# S111X.net
KiCad netlist of a schematic drawn in EAGLE
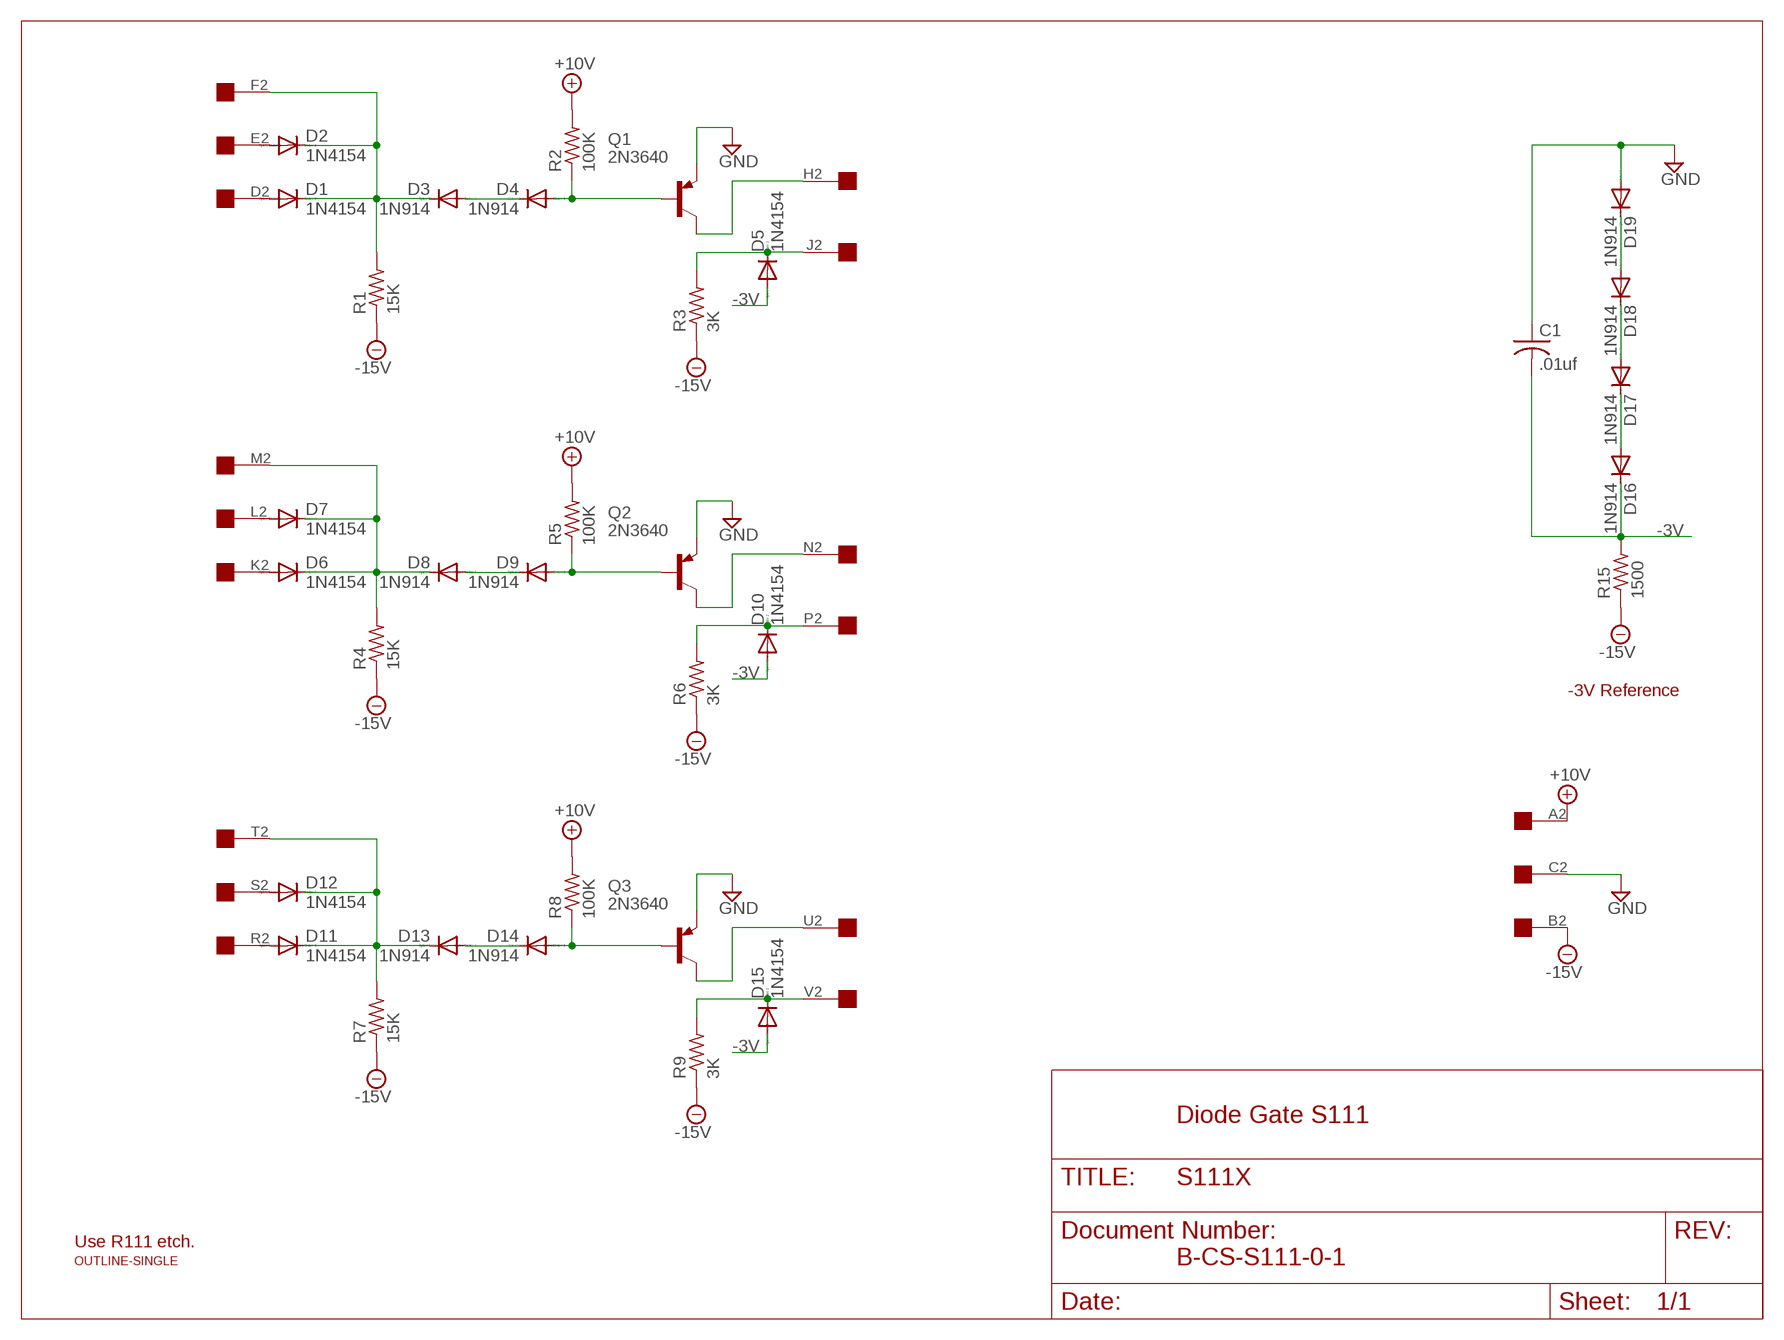
[diagram p0: schematic, sheet 1]

(export (version "E")
  (design (tool "Eeschema 10.0.6"))
  (components
    (comp (ref "C1")
      (value ".01uf")
      (footprint "eagle-import:C050-025X075")
      (libsource (lib "eagle-import") (part "C-US050-025X075"))
    )
    (comp (ref "D1")
      (value "1N4154")
      (footprint "eagle-import:DO35-10")
      (libsource (lib "eagle-import") (part "1N4148DO35-10"))
    )
    (comp (ref "D2")
      (value "1N4154")
      (footprint "eagle-import:DO35-10")
      (libsource (lib "eagle-import") (part "1N4148DO35-10"))
    )
    (comp (ref "D3")
      (value "1N914")
      (footprint "eagle-import:DO35-10")
      (libsource (lib "eagle-import") (part "1N4148DO35-10"))
    )
    (comp (ref "D4")
      (value "1N914")
      (footprint "eagle-import:DO35-10")
      (libsource (lib "eagle-import") (part "1N4148DO35-10"))
    )
    (comp (ref "D5")
      (value "1N4154")
      (footprint "eagle-import:DO35-10")
      (libsource (lib "eagle-import") (part "1N4148DO35-10"))
    )
    (comp (ref "D6")
      (value "1N4154")
      (footprint "eagle-import:DO35-10")
      (libsource (lib "eagle-import") (part "1N4148DO35-10"))
    )
    (comp (ref "D7")
      (value "1N4154")
      (footprint "eagle-import:DO35-10")
      (libsource (lib "eagle-import") (part "1N4148DO35-10"))
    )
    (comp (ref "D8")
      (value "1N914")
      (footprint "eagle-import:DO35-10")
      (libsource (lib "eagle-import") (part "1N4148DO35-10"))
    )
    (comp (ref "D9")
      (value "1N914")
      (footprint "eagle-import:DO35-10")
      (libsource (lib "eagle-import") (part "1N4148DO35-10"))
    )
    (comp (ref "D10")
      (value "1N4154")
      (footprint "eagle-import:DO35-10")
      (libsource (lib "eagle-import") (part "1N4148DO35-10"))
    )
    (comp (ref "D11")
      (value "1N4154")
      (footprint "eagle-import:DO35-10")
      (libsource (lib "eagle-import") (part "1N4148DO35-10"))
    )
    (comp (ref "D12")
      (value "1N4154")
      (footprint "eagle-import:DO35-10")
      (libsource (lib "eagle-import") (part "1N4148DO35-10"))
    )
    (comp (ref "D13")
      (value "1N914")
      (footprint "eagle-import:DO35-10")
      (libsource (lib "eagle-import") (part "1N4148DO35-10"))
    )
    (comp (ref "D14")
      (value "1N914")
      (footprint "eagle-import:DO35-10")
      (libsource (lib "eagle-import") (part "1N4148DO35-10"))
    )
    (comp (ref "D15")
      (value "1N4154")
      (footprint "eagle-import:DO35-10")
      (libsource (lib "eagle-import") (part "1N4148DO35-10"))
    )
    (comp (ref "D16")
      (value "1N914")
      (footprint "eagle-import:DO35-10")
      (libsource (lib "eagle-import") (part "1N4148DO35-10"))
    )
    (comp (ref "D17")
      (value "1N914")
      (footprint "eagle-import:DO35-10")
      (libsource (lib "eagle-import") (part "1N4148DO35-10"))
    )
    (comp (ref "D18")
      (value "1N914")
      (footprint "eagle-import:DO35-10")
      (libsource (lib "eagle-import") (part "1N4148DO35-10"))
    )
    (comp (ref "D19")
      (value "1N914")
      (footprint "eagle-import:DO35-10")
      (libsource (lib "eagle-import") (part "1N4148DO35-10"))
    )
    (comp (ref "Q1")
      (value "2N3640")
      (footprint "eagle-import:TO39")
      (libsource (lib "eagle-import") (part "2N3637"))
    )
    (comp (ref "Q2")
      (value "2N3640")
      (footprint "eagle-import:TO39")
      (libsource (lib "eagle-import") (part "2N3637"))
    )
    (comp (ref "Q3")
      (value "2N3640")
      (footprint "eagle-import:TO39")
      (libsource (lib "eagle-import") (part "2N3637"))
    )
    (comp (ref "R1")
      (value "15K")
      (footprint "eagle-import:0207_10")
      (libsource (lib "eagle-import") (part "R-US_0207/10"))
    )
    (comp (ref "R2")
      (value "100K")
      (footprint "eagle-import:0207_10")
      (libsource (lib "eagle-import") (part "R-US_0207/10"))
    )
    (comp (ref "R3")
      (value "3K")
      (footprint "eagle-import:0207_10")
      (libsource (lib "eagle-import") (part "R-US_0207/10"))
    )
    (comp (ref "R4")
      (value "15K")
      (footprint "eagle-import:0207_10")
      (libsource (lib "eagle-import") (part "R-US_0207/10"))
    )
    (comp (ref "R5")
      (value "100K")
      (footprint "eagle-import:0207_10")
      (libsource (lib "eagle-import") (part "R-US_0207/10"))
    )
    (comp (ref "R6")
      (value "3K")
      (footprint "eagle-import:0207_10")
      (libsource (lib "eagle-import") (part "R-US_0207/10"))
    )
    (comp (ref "R7")
      (value "15K")
      (footprint "eagle-import:0207_10")
      (libsource (lib "eagle-import") (part "R-US_0207/10"))
    )
    (comp (ref "R8")
      (value "100K")
      (footprint "eagle-import:0207_10")
      (libsource (lib "eagle-import") (part "R-US_0207/10"))
    )
    (comp (ref "R9")
      (value "3K")
      (footprint "eagle-import:0207_10")
      (libsource (lib "eagle-import") (part "R-US_0207/10"))
    )
    (comp (ref "R15")
      (value "1500")
      (footprint "eagle-import:0207_10")
      (libsource (lib "eagle-import") (part "R-US_0207/10"))
    )
    (comp (ref "U$1")
      (value "OUTLINE-SINGLE")
      (footprint "eagle-import:SINGLE")
      (libsource (lib "eagle-import") (part "OUTLINE-SINGLE"))
    )
    (comp (ref "U$2")
      (value "EDGE-1")
      (footprint "eagle-import:EDGE-CON1")
      (libsource (lib "eagle-import") (part "EDGE-1"))
    )
  )
  (nets
    (net (code "1") (name "+10V") (class "Default")
      (node (ref "R2") (pin "2") (pinfunction "2_2") (pintype "passive"))
      (node (ref "R5") (pin "2") (pinfunction "2_2") (pintype "passive"))
      (node (ref "R8") (pin "2") (pinfunction "2_2") (pintype "passive"))
      (node (ref "U$2") (pin "A2") (pinfunction "1_A2") (pintype "bidirectional"))
    )
    (net (code "2") (name "-15V") (class "Default")
      (node (ref "R1") (pin "1") (pinfunction "1_1") (pintype "passive"))
      (node (ref "R15") (pin "1") (pinfunction "1_1") (pintype "passive"))
      (node (ref "R3") (pin "1") (pinfunction "1_1") (pintype "passive"))
      (node (ref "R4") (pin "1") (pinfunction "1_1") (pintype "passive"))
      (node (ref "R6") (pin "1") (pinfunction "1_1") (pintype "passive"))
      (node (ref "R7") (pin "1") (pinfunction "1_1") (pintype "passive"))
      (node (ref "R9") (pin "1") (pinfunction "1_1") (pintype "passive"))
      (node (ref "U$2") (pin "B2") (pinfunction "1_B2") (pintype "bidirectional"))
    )
    (net (code "3") (name "/-3V") (class "Default")
      (node (ref "C1") (pin "2") (pinfunction "2_2") (pintype "passive"))
      (node (ref "D10") (pin "A") (pinfunction "A_A") (pintype "passive"))
      (node (ref "D15") (pin "A") (pinfunction "A_A") (pintype "passive"))
      (node (ref "D16") (pin "C") (pinfunction "C_C") (pintype "passive"))
      (node (ref "D5") (pin "A") (pinfunction "A_A") (pintype "passive"))
      (node (ref "R15") (pin "2") (pinfunction "2_2") (pintype "passive"))
    )
    (net (code "4") (name "GND") (class "Default")
      (node (ref "C1") (pin "1") (pinfunction "1_1") (pintype "passive"))
      (node (ref "D19") (pin "A") (pinfunction "A_A") (pintype "passive"))
      (node (ref "Q1") (pin "1") (pinfunction "E_1") (pintype "passive"))
      (node (ref "Q2") (pin "1") (pinfunction "E_1") (pintype "passive"))
      (node (ref "Q3") (pin "1") (pinfunction "E_1") (pintype "passive"))
      (node (ref "U$2") (pin "C2") (pinfunction "1_C2") (pintype "bidirectional"))
    )
    (net (code "5") (name "Net-(D3-PadA)") (class "Default")
      (node (ref "D3") (pin "A") (pinfunction "A_A") (pintype "passive"))
      (node (ref "D4") (pin "C") (pinfunction "C_C") (pintype "passive"))
    )
    (net (code "6") (name "Net-(D8-PadA)") (class "Default")
      (node (ref "D8") (pin "A") (pinfunction "A_A") (pintype "passive"))
      (node (ref "D9") (pin "C") (pinfunction "C_C") (pintype "passive"))
    )
    (net (code "7") (name "Net-(D13-PadA)") (class "Default")
      (node (ref "D13") (pin "A") (pinfunction "A_A") (pintype "passive"))
      (node (ref "D14") (pin "C") (pinfunction "C_C") (pintype "passive"))
    )
    (net (code "8") (name "Net-(D16-PadA)") (class "Default")
      (node (ref "D16") (pin "A") (pinfunction "A_A") (pintype "passive"))
      (node (ref "D17") (pin "C") (pinfunction "C_C") (pintype "passive"))
    )
    (net (code "9") (name "Net-(D17-PadA)") (class "Default")
      (node (ref "D17") (pin "A") (pinfunction "A_A") (pintype "passive"))
      (node (ref "D18") (pin "C") (pinfunction "C_C") (pintype "passive"))
    )
    (net (code "10") (name "Net-(D18-PadA)") (class "Default")
      (node (ref "D18") (pin "A") (pinfunction "A_A") (pintype "passive"))
      (node (ref "D19") (pin "C") (pinfunction "C_C") (pintype "passive"))
    )
    (net (code "11") (name "Net-(Q1-B)") (class "Default")
      (node (ref "D4") (pin "A") (pinfunction "A_A") (pintype "passive"))
      (node (ref "Q1") (pin "2") (pinfunction "B_2") (pintype "passive"))
      (node (ref "R2") (pin "1") (pinfunction "1_1") (pintype "passive"))
    )
    (net (code "12") (name "Net-(Q1-C)") (class "Default")
      (node (ref "Q1") (pin "3") (pinfunction "C_3") (pintype "passive"))
      (node (ref "U$2") (pin "H2") (pinfunction "1_H2") (pintype "bidirectional"))
    )
    (net (code "13") (name "Net-(Q2-B)") (class "Default")
      (node (ref "D9") (pin "A") (pinfunction "A_A") (pintype "passive"))
      (node (ref "Q2") (pin "2") (pinfunction "B_2") (pintype "passive"))
      (node (ref "R5") (pin "1") (pinfunction "1_1") (pintype "passive"))
    )
    (net (code "14") (name "Net-(Q2-C)") (class "Default")
      (node (ref "Q2") (pin "3") (pinfunction "C_3") (pintype "passive"))
      (node (ref "U$2") (pin "N2") (pinfunction "1_N2") (pintype "bidirectional"))
    )
    (net (code "15") (name "Net-(Q3-B)") (class "Default")
      (node (ref "D14") (pin "A") (pinfunction "A_A") (pintype "passive"))
      (node (ref "Q3") (pin "2") (pinfunction "B_2") (pintype "passive"))
      (node (ref "R8") (pin "1") (pinfunction "1_1") (pintype "passive"))
    )
    (net (code "16") (name "Net-(Q3-C)") (class "Default")
      (node (ref "Q3") (pin "3") (pinfunction "C_3") (pintype "passive"))
      (node (ref "U$2") (pin "U2") (pinfunction "1_U2") (pintype "bidirectional"))
    )
    (net (code "17") (name "Net-(U$2D-1)") (class "Default")
      (node (ref "D1") (pin "A") (pinfunction "A_A") (pintype "passive"))
      (node (ref "U$2") (pin "D2") (pinfunction "1_D2") (pintype "bidirectional"))
    )
    (net (code "18") (name "Net-(U$2E-1)") (class "Default")
      (node (ref "D2") (pin "A") (pinfunction "A_A") (pintype "passive"))
      (node (ref "U$2") (pin "E2") (pinfunction "1_E2") (pintype "bidirectional"))
    )
    (net (code "19") (name "Net-(U$2F-1)") (class "Default")
      (node (ref "D1") (pin "C") (pinfunction "C_C") (pintype "passive"))
      (node (ref "D2") (pin "C") (pinfunction "C_C") (pintype "passive"))
      (node (ref "D3") (pin "C") (pinfunction "C_C") (pintype "passive"))
      (node (ref "R1") (pin "2") (pinfunction "2_2") (pintype "passive"))
      (node (ref "U$2") (pin "F2") (pinfunction "1_F2") (pintype "bidirectional"))
    )
    (net (code "20") (name "Net-(U$2H-1)") (class "Default")
      (node (ref "D5") (pin "C") (pinfunction "C_C") (pintype "passive"))
      (node (ref "R3") (pin "2") (pinfunction "2_2") (pintype "passive"))
      (node (ref "U$2") (pin "J2") (pinfunction "1_J2") (pintype "bidirectional"))
    )
    (net (code "21") (name "Net-(U$2I-1)") (class "Default")
      (node (ref "D6") (pin "A") (pinfunction "A_A") (pintype "passive"))
      (node (ref "U$2") (pin "K2") (pinfunction "1_K2") (pintype "bidirectional"))
    )
    (net (code "22") (name "Net-(U$2J-1)") (class "Default")
      (node (ref "D7") (pin "A") (pinfunction "A_A") (pintype "passive"))
      (node (ref "U$2") (pin "L2") (pinfunction "1_L2") (pintype "bidirectional"))
    )
    (net (code "23") (name "Net-(U$2K-1)") (class "Default")
      (node (ref "D6") (pin "C") (pinfunction "C_C") (pintype "passive"))
      (node (ref "D7") (pin "C") (pinfunction "C_C") (pintype "passive"))
      (node (ref "D8") (pin "C") (pinfunction "C_C") (pintype "passive"))
      (node (ref "R4") (pin "2") (pinfunction "2_2") (pintype "passive"))
      (node (ref "U$2") (pin "M2") (pinfunction "1_M2") (pintype "bidirectional"))
    )
    (net (code "24") (name "Net-(U$2M-1)") (class "Default")
      (node (ref "D10") (pin "C") (pinfunction "C_C") (pintype "passive"))
      (node (ref "R6") (pin "2") (pinfunction "2_2") (pintype "passive"))
      (node (ref "U$2") (pin "P2") (pinfunction "1_P2") (pintype "bidirectional"))
    )
    (net (code "25") (name "Net-(U$2N-1)") (class "Default")
      (node (ref "D11") (pin "A") (pinfunction "A_A") (pintype "passive"))
      (node (ref "U$2") (pin "R2") (pinfunction "1_R2") (pintype "bidirectional"))
    )
    (net (code "26") (name "Net-(U$2O-1)") (class "Default")
      (node (ref "D12") (pin "A") (pinfunction "A_A") (pintype "passive"))
      (node (ref "U$2") (pin "S2") (pinfunction "1_S2") (pintype "bidirectional"))
    )
    (net (code "27") (name "Net-(U$2P-1)") (class "Default")
      (node (ref "D11") (pin "C") (pinfunction "C_C") (pintype "passive"))
      (node (ref "D12") (pin "C") (pinfunction "C_C") (pintype "passive"))
      (node (ref "D13") (pin "C") (pinfunction "C_C") (pintype "passive"))
      (node (ref "R7") (pin "2") (pinfunction "2_2") (pintype "passive"))
      (node (ref "U$2") (pin "T2") (pinfunction "1_T2") (pintype "bidirectional"))
    )
    (net (code "28") (name "Net-(U$2R-1)") (class "Default")
      (node (ref "D15") (pin "C") (pinfunction "C_C") (pintype "passive"))
      (node (ref "R9") (pin "2") (pinfunction "2_2") (pintype "passive"))
      (node (ref "U$2") (pin "V2") (pinfunction "1_V2") (pintype "bidirectional"))
    )
  )
)
